# FordACPAUX.net
KiCad netlist of a schematic drawn in EAGLE
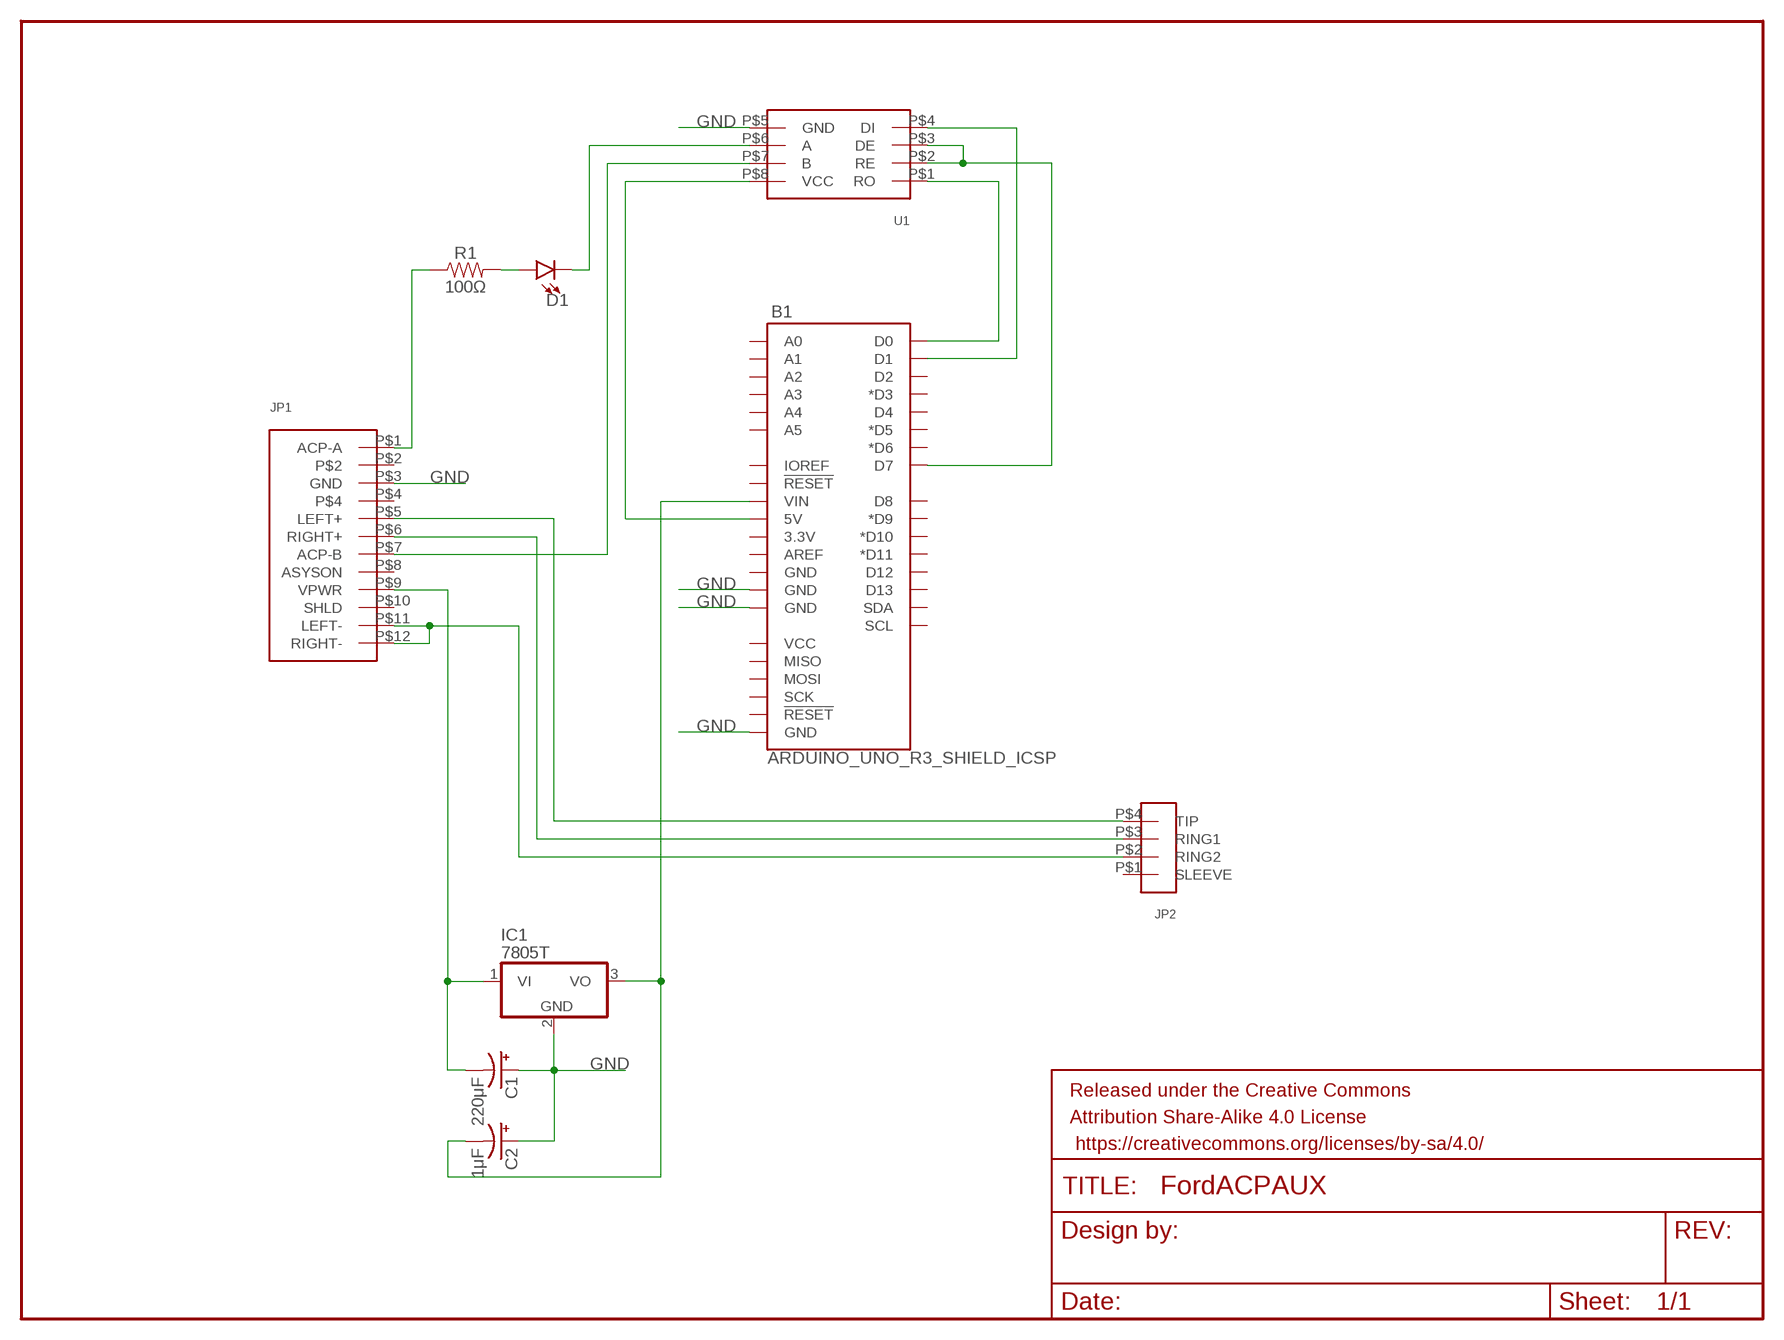
[diagram p0: schematic, sheet 1]

(export (version "E")
  (design (tool "Eeschema 10.0.6"))
  (components
    (comp (ref "B1")
      (value "ARDUINO_UNO_R3_SHIELD_ICSP")
      (footprint "eagle-import:UNO_R3_SHIELD_ICSP")
      (libsource (lib "eagle-import") (part "ARDUINO_UNO_R3_SHIELD_ICSP"))
    )
    (comp (ref "C1")
      (value "220μF")
      (footprint "eagle-import:E2,5-7")
      (libsource (lib "eagle-import") (part "CPOL-USE2.5-7"))
    )
    (comp (ref "C2")
      (value "1μF")
      (footprint "eagle-import:E2-4")
      (libsource (lib "eagle-import") (part "CPOL-USE2-4"))
    )
    (comp (ref "D1")
      (value "LED3MM")
      (footprint "eagle-import:LED_3MM")
      (libsource (lib "eagle-import") (part "LED3MM"))
    )
    (comp (ref "FRAME1")
      (value "FRAME-LETTER")
      (footprint "eagle-import:CREATIVE_COMMONS")
      (libsource (lib "eagle-import") (part "FRAME-LETTER"))
    )
    (comp (ref "IC1")
      (value "7805T")
      (footprint "eagle-import:TO220H")
      (libsource (lib "eagle-import") (part "78T05"))
    )
    (comp (ref "JP1")
      (value "AMP-174051-2_040_MULTILOCK")
      (footprint "eagle-import:AMP_174051-2_040_MULTILOCK")
      (libsource (lib "eagle-import") (part "AMP-174051-2_040_MULTILOCK"))
    )
    (comp (ref "JP2")
      (value "TRRS_JACKBREAKOUT")
      (footprint "eagle-import:HEADER-4-PIN-TRRS-JACK-BREAKOUT")
      (libsource (lib "eagle-import") (part "TRRS_JACKBREAKOUT"))
    )
    (comp (ref "R1")
      (value "100Ω")
      (footprint "eagle-import:AXIAL-0.3")
      (libsource (lib "eagle-import") (part "RESISTORAXIAL-0.3"))
    )
    (comp (ref "U1")
      (value "MAX485_TTL_TO_RS_485_MODULE")
      (footprint "eagle-import:MAX485_TTL_TO_RS_485_MODULE")
      (libsource (lib "eagle-import") (part "MAX485_TTL_TO_RS_485_MODULE"))
    )
  )
  (nets
    (net (code "1") (name "/GND") (class "Default")
      (node (ref "B1") (pin "GND@0") (pinfunction "GND_GND@0") (pintype "bidirectional"))
      (node (ref "B1") (pin "GND@1") (pinfunction "GND_GND@1") (pintype "bidirectional"))
      (node (ref "B1") (pin "GND_ICSP") (pinfunction "GND_GND_ICSP") (pintype "bidirectional"))
      (node (ref "C1") (pin "+") (pinfunction "+_+") (pintype "passive"))
      (node (ref "C2") (pin "+") (pinfunction "+_+") (pintype "passive"))
      (node (ref "IC1") (pin "2") (pinfunction "GND_2") (pintype "passive"))
      (node (ref "JP1") (pin "P$3") (pinfunction "GND_P$3") (pintype "power_in"))
      (node (ref "U1") (pin "P$5") (pinfunction "GND_P$5") (pintype "power_in"))
    )
    (net (code "2") (name "Net-(B1-D0)") (class "Default")
      (node (ref "B1") (pin "RX") (pinfunction "D0_RX") (pintype "bidirectional"))
      (node (ref "U1") (pin "P$1") (pinfunction "RO_P$1") (pintype "output"))
    )
    (net (code "3") (name "Net-(B1-D1)") (class "Default")
      (node (ref "B1") (pin "TX") (pinfunction "D1_TX") (pintype "bidirectional"))
      (node (ref "U1") (pin "P$4") (pinfunction "DI_P$4") (pintype "input"))
    )
    (net (code "4") (name "Net-(D1-C)") (class "Default")
      (node (ref "D1") (pin "K") (pinfunction "C_K") (pintype "passive"))
      (node (ref "U1") (pin "P$6") (pinfunction "A_P$6") (pintype "bidirectional"))
    )
    (net (code "5") (name "Net-(IC1-VI)") (class "Default")
      (node (ref "C1") (pin "-") (pinfunction "-_-") (pintype "passive"))
      (node (ref "IC1") (pin "1") (pinfunction "VI_1") (pintype "input"))
      (node (ref "JP1") (pin "P$9") (pinfunction "VPWR_P$9") (pintype "power_in"))
    )
    (net (code "6") (name "Net-(IC1-VO)") (class "Default")
      (node (ref "B1") (pin "VIN") (pinfunction "VIN_VIN") (pintype "bidirectional"))
      (node (ref "C2") (pin "-") (pinfunction "-_-") (pintype "passive"))
      (node (ref "IC1") (pin "3") (pinfunction "VO_3") (pintype "passive"))
    )
    (net (code "7") (name "Net-(JP1-ACP-A)") (class "Default")
      (node (ref "JP1") (pin "P$1") (pinfunction "ACP-A_P$1") (pintype "bidirectional"))
      (node (ref "R1") (pin "P$1") (pinfunction "1_P$1") (pintype "passive"))
    )
    (net (code "8") (name "Net-(JP1-ACP-B)") (class "Default")
      (node (ref "JP1") (pin "P$7") (pinfunction "ACP-B_P$7") (pintype "bidirectional"))
      (node (ref "U1") (pin "P$7") (pinfunction "B_P$7") (pintype "bidirectional"))
    )
    (net (code "9") (name "Net-(JP1-LEFT+)") (class "Default")
      (node (ref "JP1") (pin "P$5") (pinfunction "LEFT+_P$5") (pintype "output"))
      (node (ref "JP2") (pin "P$4") (pinfunction "TIP_P$4") (pintype "bidirectional"))
    )
    (net (code "10") (name "Net-(JP1-LEFT-)") (class "Default")
      (node (ref "JP1") (pin "P$11") (pinfunction "LEFT-_P$11") (pintype "input"))
      (node (ref "JP1") (pin "P$12") (pinfunction "RIGHT-_P$12") (pintype "input"))
      (node (ref "JP2") (pin "P$2") (pinfunction "RING2_P$2") (pintype "bidirectional"))
    )
    (net (code "11") (name "Net-(JP1-RIGHT+)") (class "Default")
      (node (ref "JP1") (pin "P$6") (pinfunction "RIGHT+_P$6") (pintype "output"))
      (node (ref "JP2") (pin "P$3") (pinfunction "RING1_P$3") (pintype "bidirectional"))
    )
    (net (code "12") (name "Net-(R1-2)") (class "Default")
      (node (ref "D1") (pin "A") (pinfunction "A_A") (pintype "passive"))
      (node (ref "R1") (pin "P$2") (pinfunction "2_P$2") (pintype "passive"))
    )
    (net (code "13") (name "Net-(U1-DE)") (class "Default")
      (node (ref "B1") (pin "D7") (pinfunction "D7_D7") (pintype "bidirectional"))
      (node (ref "U1") (pin "P$2") (pinfunction "RE_P$2") (pintype "bidirectional"))
      (node (ref "U1") (pin "P$3") (pinfunction "DE_P$3") (pintype "bidirectional"))
    )
    (net (code "14") (name "Net-(U1-VCC)") (class "Default")
      (node (ref "B1") (pin "5V") (pinfunction "5V_5V") (pintype "bidirectional"))
      (node (ref "U1") (pin "P$8") (pinfunction "VCC_P$8") (pintype "power_in"))
    )
    (net (code "15") (name "unconnected-(B1-*D3-PadD3)") (class "Default")
      (node (ref "B1") (pin "D3") (pinfunction "*D3_D3") (pintype "bidirectional"))
    )
    (net (code "16") (name "unconnected-(B1-*D5-PadD5)") (class "Default")
      (node (ref "B1") (pin "D5") (pinfunction "*D5_D5") (pintype "bidirectional"))
    )
    (net (code "17") (name "unconnected-(B1-*D6-PadD6)") (class "Default")
      (node (ref "B1") (pin "D6") (pinfunction "*D6_D6") (pintype "bidirectional"))
    )
    (net (code "18") (name "unconnected-(B1-*D9-PadD9)") (class "Default")
      (node (ref "B1") (pin "D9") (pinfunction "*D9_D9") (pintype "bidirectional"))
    )
    (net (code "19") (name "unconnected-(B1-*D10-PadD10)") (class "Default")
      (node (ref "B1") (pin "D10") (pinfunction "*D10_D10") (pintype "bidirectional"))
    )
    (net (code "20") (name "unconnected-(B1-*D11-PadD11)") (class "Default")
      (node (ref "B1") (pin "D11") (pinfunction "*D11_D11") (pintype "bidirectional"))
    )
    (net (code "21") (name "unconnected-(B1-GND-PadGND@2)") (class "Default")
      (node (ref "B1") (pin "GND@2") (pinfunction "GND_GND@2") (pintype "bidirectional"))
    )
    (net (code "22") (name "unconnected-(B1-Pad3.3V)") (class "Default")
      (node (ref "B1") (pin "3.3V") (pinfunction "3.3V_3.3V") (pintype "bidirectional"))
    )
    (net (code "23") (name "unconnected-(B1-PadA0)") (class "Default")
      (node (ref "B1") (pin "A0") (pinfunction "A0_A0") (pintype "bidirectional"))
    )
    (net (code "24") (name "unconnected-(B1-PadA1)") (class "Default")
      (node (ref "B1") (pin "A1") (pinfunction "A1_A1") (pintype "bidirectional"))
    )
    (net (code "25") (name "unconnected-(B1-PadA2)") (class "Default")
      (node (ref "B1") (pin "A2") (pinfunction "A2_A2") (pintype "bidirectional"))
    )
    (net (code "26") (name "unconnected-(B1-PadA3)") (class "Default")
      (node (ref "B1") (pin "A3") (pinfunction "A3_A3") (pintype "bidirectional"))
    )
    (net (code "27") (name "unconnected-(B1-PadA4)") (class "Default")
      (node (ref "B1") (pin "A4") (pinfunction "A4_A4") (pintype "bidirectional"))
    )
    (net (code "28") (name "unconnected-(B1-PadA5)") (class "Default")
      (node (ref "B1") (pin "A5") (pinfunction "A5_A5") (pintype "bidirectional"))
    )
    (net (code "29") (name "unconnected-(B1-PadAREF)") (class "Default")
      (node (ref "B1") (pin "AREF") (pinfunction "AREF_AREF") (pintype "bidirectional"))
    )
    (net (code "30") (name "unconnected-(B1-PadD2)") (class "Default")
      (node (ref "B1") (pin "D2") (pinfunction "D2_D2") (pintype "bidirectional"))
    )
    (net (code "31") (name "unconnected-(B1-PadD4)") (class "Default")
      (node (ref "B1") (pin "D4") (pinfunction "D4_D4") (pintype "bidirectional"))
    )
    (net (code "32") (name "unconnected-(B1-PadD8)") (class "Default")
      (node (ref "B1") (pin "D8") (pinfunction "D8_D8") (pintype "bidirectional"))
    )
    (net (code "33") (name "unconnected-(B1-PadD12)") (class "Default")
      (node (ref "B1") (pin "D12") (pinfunction "D12_D12") (pintype "bidirectional"))
    )
    (net (code "34") (name "unconnected-(B1-PadD13)") (class "Default")
      (node (ref "B1") (pin "D13") (pinfunction "D13_D13") (pintype "bidirectional"))
    )
    (net (code "35") (name "unconnected-(B1-PadIOREF)") (class "Default")
      (node (ref "B1") (pin "IOREF") (pinfunction "IOREF_IOREF") (pintype "bidirectional"))
    )
    (net (code "36") (name "unconnected-(B1-PadMISO)") (class "Default")
      (node (ref "B1") (pin "MISO") (pinfunction "MISO_MISO") (pintype "bidirectional"))
    )
    (net (code "37") (name "unconnected-(B1-PadMOSI)") (class "Default")
      (node (ref "B1") (pin "MOSI") (pinfunction "MOSI_MOSI") (pintype "bidirectional"))
    )
    (net (code "38") (name "unconnected-(B1-PadSCK)") (class "Default")
      (node (ref "B1") (pin "SCK") (pinfunction "SCK_SCK") (pintype "bidirectional"))
    )
    (net (code "39") (name "unconnected-(B1-PadSCL)") (class "Default")
      (node (ref "B1") (pin "SCL") (pinfunction "SCL_SCL") (pintype "bidirectional"))
    )
    (net (code "40") (name "unconnected-(B1-PadSDA)") (class "Default")
      (node (ref "B1") (pin "SDA") (pinfunction "SDA_SDA") (pintype "bidirectional"))
    )
    (net (code "41") (name "unconnected-(B1-VCC-Pad5V_ICSP)") (class "Default")
      (node (ref "B1") (pin "5V_ICSP") (pinfunction "VCC_5V_ICSP") (pintype "bidirectional"))
    )
    (net (code "42") (name "unconnected-(B1-~{RESET}-PadRES)") (class "Default")
      (node (ref "B1") (pin "RES") (pinfunction "~{RESET}_RES") (pintype "bidirectional"))
    )
    (net (code "43") (name "unconnected-(B1-~{RESET}-PadRST_ICSP)") (class "Default")
      (node (ref "B1") (pin "RST_ICSP") (pinfunction "~{RESET}_RST_ICSP") (pintype "bidirectional"))
    )
    (net (code "44") (name "unconnected-(JP1-ASYSON-PadP$8)") (class "Default")
      (node (ref "JP1") (pin "P$8") (pinfunction "ASYSON_P$8") (pintype "input"))
    )
    (net (code "45") (name "unconnected-(JP1-PadP$2)") (class "Default")
      (node (ref "JP1") (pin "P$2") (pinfunction "P$2_P$2") (pintype "no_connect"))
    )
    (net (code "46") (name "unconnected-(JP1-PadP$4)") (class "Default")
      (node (ref "JP1") (pin "P$4") (pinfunction "P$4_P$4") (pintype "no_connect"))
    )
    (net (code "47") (name "unconnected-(JP1-SHLD-PadP$10)") (class "Default")
      (node (ref "JP1") (pin "P$10") (pinfunction "SHLD_P$10") (pintype "passive"))
    )
    (net (code "48") (name "unconnected-(JP2-SLEEVE-PadP$1)") (class "Default")
      (node (ref "JP2") (pin "P$1") (pinfunction "SLEEVE_P$1") (pintype "bidirectional"))
    )
  )
)
